# LDR_SHEET.net
KiCad netlist of a schematic drawn in Altium Designer
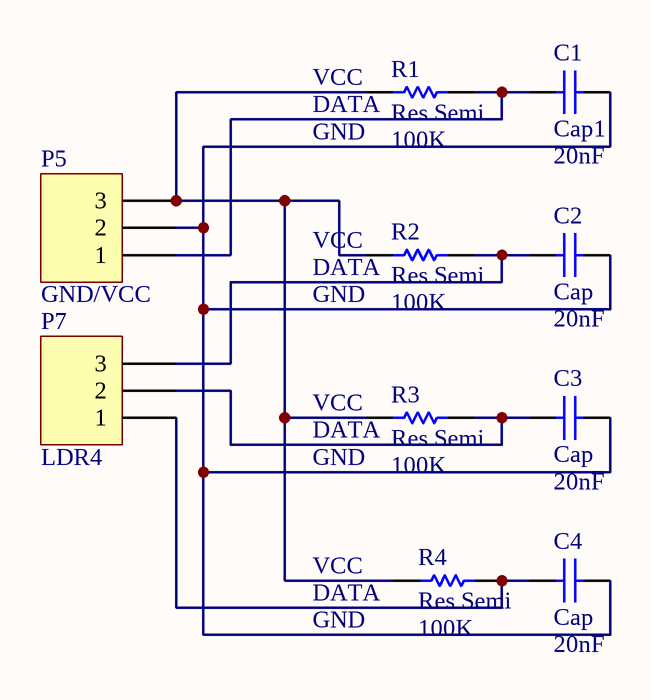
[diagram p0: LDR SHEET.SchDoc]

(export (version "E")
  (design (tool "Eeschema 10.0.6"))
  (components
    (comp (ref "C1")
      (value "Cap1")
      (footprint "RAD-0.3")
      (description "Capacitor")
      (fields (field (name "ALTIUM_VALUE") "20nF") (field (name "PUBLISHER") "Altium Limited"))
      (libsource (lib "Miscellaneous Devices") (part "Cap"))
    )
    (comp (ref "C2")
      (value "Cap")
      (footprint "RAD-0.3")
      (description "Capacitor")
      (fields (field (name "ALTIUM_VALUE") "20nF") (field (name "PUBLISHER") "Altium Limited"))
      (libsource (lib "Miscellaneous Devices") (part "Cap"))
    )
    (comp (ref "C3")
      (value "Cap")
      (footprint "RAD-0.3")
      (description "Capacitor")
      (fields (field (name "ALTIUM_VALUE") "20nF") (field (name "PUBLISHER") "Altium Limited"))
      (libsource (lib "Miscellaneous Devices") (part "Cap"))
    )
    (comp (ref "C4")
      (value "Cap")
      (footprint "RAD-0.3")
      (description "Capacitor")
      (fields (field (name "ALTIUM_VALUE") "20nF") (field (name "PUBLISHER") "Altium Limited"))
      (libsource (lib "Miscellaneous Devices") (part "Cap"))
    )
    (comp (ref "P5")
      (value "GND/VCC")
      (footprint "HDR1X3")
      (description "Header, 3-Pin")
      (fields (field (name "PUBLISHER") "Altium Limited"))
      (libsource (lib "Miscellaneous Connectors") (part "Header 3"))
    )
    (comp (ref "P7")
      (value "LDR4")
      (footprint "HDR1X3")
      (description "Header, 3-Pin")
      (fields (field (name "PUBLISHER") "Altium Limited"))
      (libsource (lib "Miscellaneous Connectors") (part "Header 3"))
    )
    (comp (ref "R1")
      (value "Res Semi")
      (footprint "AXIAL-0.5")
      (description "Semiconductor Resistor")
      (fields (field (name "ALTIUM_VALUE") "100K") (field (name "PUBLISHER") "Altium Limited"))
      (libsource (lib "Miscellaneous Devices") (part "Res Semi"))
    )
    (comp (ref "R2")
      (value "Res Semi")
      (footprint "AXIAL-0.5")
      (description "Semiconductor Resistor")
      (fields (field (name "ALTIUM_VALUE") "100K") (field (name "PUBLISHER") "Altium Limited"))
      (libsource (lib "Miscellaneous Devices") (part "Res Semi"))
    )
    (comp (ref "R3")
      (value "Res Semi")
      (footprint "AXIAL-0.5")
      (description "Semiconductor Resistor")
      (fields (field (name "ALTIUM_VALUE") "100K") (field (name "PUBLISHER") "Altium Limited"))
      (libsource (lib "Miscellaneous Devices") (part "Res Semi"))
    )
    (comp (ref "R4")
      (value "Res Semi")
      (footprint "AXIAL-0.5")
      (description "Semiconductor Resistor")
      (fields (field (name "ALTIUM_VALUE") "100K") (field (name "PUBLISHER") "Altium Limited"))
      (libsource (lib "Miscellaneous Devices") (part "Res Semi"))
    )
  )
  (nets
    (net (code "1") (name "Net-(C1-Pad1)") (class "Default")
      (node (ref "C1") (pin "1") (pinfunction "1_1") (pintype "passive"))
      (node (ref "P5") (pin "1") (pinfunction "1_1") (pintype "passive"))
      (node (ref "R1") (pin "1") (pinfunction "1_1") (pintype "passive"))
    )
    (net (code "2") (name "Net-(C1-Pad2)") (class "Default")
      (node (ref "C1") (pin "2") (pinfunction "2_2") (pintype "passive"))
      (node (ref "C2") (pin "2") (pinfunction "2_2") (pintype "passive"))
      (node (ref "C3") (pin "2") (pinfunction "2_2") (pintype "passive"))
      (node (ref "C4") (pin "2") (pinfunction "2_2") (pintype "passive"))
      (node (ref "P5") (pin "2") (pinfunction "2_2") (pintype "passive"))
    )
    (net (code "3") (name "Net-(C2-Pad1)") (class "Default")
      (node (ref "C2") (pin "1") (pinfunction "1_1") (pintype "passive"))
      (node (ref "P7") (pin "3") (pinfunction "3_3") (pintype "passive"))
      (node (ref "R2") (pin "1") (pinfunction "1_1") (pintype "passive"))
    )
    (net (code "4") (name "Net-(C3-Pad1)") (class "Default")
      (node (ref "C3") (pin "1") (pinfunction "1_1") (pintype "passive"))
      (node (ref "P7") (pin "2") (pinfunction "2_2") (pintype "passive"))
      (node (ref "R3") (pin "1") (pinfunction "1_1") (pintype "passive"))
    )
    (net (code "5") (name "Net-(C4-Pad1)") (class "Default")
      (node (ref "C4") (pin "1") (pinfunction "1_1") (pintype "passive"))
      (node (ref "P7") (pin "1") (pinfunction "1_1") (pintype "passive"))
      (node (ref "R4") (pin "1") (pinfunction "1_1") (pintype "passive"))
    )
    (net (code "6") (name "Net-(P5-Pad3)") (class "Default")
      (node (ref "P5") (pin "3") (pinfunction "3_3") (pintype "passive"))
      (node (ref "R1") (pin "2") (pinfunction "2_2") (pintype "passive"))
      (node (ref "R2") (pin "2") (pinfunction "2_2") (pintype "passive"))
      (node (ref "R3") (pin "2") (pinfunction "2_2") (pintype "passive"))
      (node (ref "R4") (pin "2") (pinfunction "2_2") (pintype "passive"))
    )
  )
)
